# Sensors.net
KiCad netlist of a schematic drawn in Altium Designer
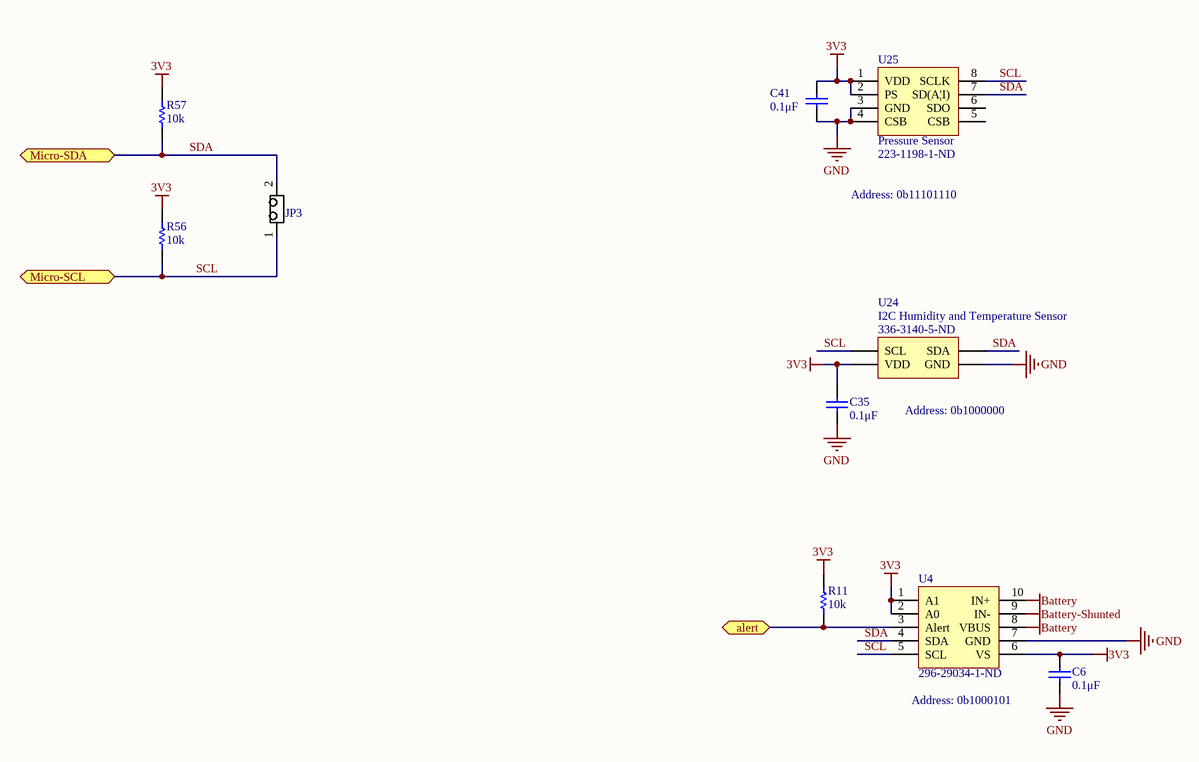
[diagram p0: Sensors.SchDoc]

(export (version "E")
  (design (tool "Eeschema 10.0.6"))
  (components
    (comp (ref "C6")
      (value "0.1μF")
      (footprint "CAPC1608N(0603\")")
      (description "Capacitor, Ceramic, 100V, +/- 10%, 0603 SMD, X7R")
      (fields
        (field (name "MFG") "TDK")
        (field (name "PUBLISHER") "AUVic")
        (field (name "CREATED BY") "Ashwin Sira")
      )
      (libsource (lib "AUVic_Integrated_Library_Capacitors") (part "0.1uF 100V 0603 SMD, Ceramic"))
    )
    (comp (ref "C35")
      (value "0.1μF")
      (footprint "CAPC1608N(0603\")")
      (description "Capacitor, Ceramic, 100V, +/- 10%, 0603 SMD, X7R")
      (fields
        (field (name "MFG") "TDK")
        (field (name "PUBLISHER") "AUVic")
        (field (name "CREATED BY") "Ashwin Sira")
      )
      (libsource (lib "AUVic_Integrated_Library_Capacitors") (part "0.1uF 100V 0603 SMD, Ceramic"))
    )
    (comp (ref "C41")
      (value "0.1μF")
      (footprint "CAPC1608N(0603\")")
      (description "Capacitor, Ceramic, 100V, +/- 10%, 0603 SMD, X7R")
      (fields
        (field (name "MFG") "TDK")
        (field (name "PUBLISHER") "AUVic")
        (field (name "CREATED BY") "Ashwin Sira")
      )
      (libsource (lib "AUVic_Integrated_Library_Capacitors") (part "0.1uF 100V 0603 SMD, Ceramic"))
    )
    (comp (ref "JP3")
      (value "1X2 Pin Head")
      (footprint "2X1 Males Header")
      (fields (field (name "MADE BY") "Andy Bates"))
      (libsource (lib "AUVic_Schematic_Library_Connectors") (part "1x2 Male Header"))
    )
    (comp (ref "R11")
      (value "10k")
      (footprint "RESC1608N(0603\")")
      (description "10kR, 1%, 1/10W, 0603 SMD")
      (fields (field (name "MADE BY") "Ashwin Sira"))
      (libsource (lib "AUVic_Integrated_Library_Resistors") (part "10kR, 1%, 1/10W, 0603 SMD"))
    )
    (comp (ref "R56")
      (value "10k")
      (footprint "RESC1608N(0603\")")
      (description "10kR, 1%, 1/10W, 0603 SMD")
      (fields (field (name "MADE BY") "Ashwin Sira"))
      (libsource (lib "AUVic_Integrated_Library_Resistors") (part "10kR, 1%, 1/10W, 0603 SMD"))
    )
    (comp (ref "R57")
      (value "10k")
      (footprint "RESC1608N(0603\")")
      (description "10kR, 1%, 1/10W, 0603 SMD")
      (fields (field (name "MADE BY") "Ashwin Sira"))
      (libsource (lib "AUVic_Integrated_Library_Resistors") (part "10kR, 1%, 1/10W, 0603 SMD"))
    )
    (comp (ref "U4")
      (value "High side current sensor")
      (footprint "MSOP-10")
      (description "0-36V High side current sensor")
      (fields (field (name "SUPPLIER PART NUMBER 1") "296-29034-1-ND") (field (name "MADE BY") "Andy Bates"))
      (libsource (lib "AUVic_Schematic_Library_Sensors") (part "INA226AIDGSR, Current Sensor, High Side"))
    )
    (comp (ref "U24")
      (value "I2C Humidity and Temperature Sensor")
      (footprint "QFN-6")
      (fields (field (name "SUPPLIER PART NUMBER 1") "336-3140-5-ND") (field (name "MADE BY") "Andy Bates"))
      (libsource (lib "AUVic_Integrated_Library_Sensors") (part "Si700XX"))
    )
    (comp (ref "U25")
      (value "Pressure Sensor")
      (footprint "TE Pressure Sensor (MS560702BA03-50)")
      (description "1kPa to 120 kPa")
      (fields (field (name "SUPPLIER PART NUMBER 1") "223-1198-1-ND") (field (name "MADE BY") "Andy Bates"))
      (libsource (lib "AUVic_Schematic_Library_Sensors") (part "MS560702BA03-50 Pressure Sensor"))
    )
  )
  (nets
    (net (code "1") (name "/SCL") (class "Default")
      (node (ref "JP3") (pin "1") (pinfunction "1_1") (pintype "passive"))
      (node (ref "R56") (pin "1") (pinfunction "1_1") (pintype "passive"))
      (node (ref "U24") (pin "6") (pinfunction "SCL_6") (pintype "passive"))
      (node (ref "U25") (pin "8") (pinfunction "SCLK_8") (pintype "passive"))
      (node (ref "U4") (pin "5") (pinfunction "SCL_5") (pintype "passive"))
    )
    (net (code "2") (name "/SDA") (class "Default")
      (node (ref "JP3") (pin "2") (pinfunction "2_2") (pintype "passive"))
      (node (ref "R57") (pin "1") (pinfunction "1_1") (pintype "passive"))
      (node (ref "U24") (pin "1") (pinfunction "SDA_1") (pintype "passive"))
      (node (ref "U25") (pin "7") (pinfunction "SD(A¦I)_7") (pintype "passive"))
      (node (ref "U4") (pin "4") (pinfunction "SDA_4") (pintype "passive"))
    )
    (net (code "3") (name "/alert") (class "Default")
      (node (ref "R11") (pin "1") (pinfunction "1_1") (pintype "passive"))
      (node (ref "U4") (pin "3") (pinfunction "Alert_3") (pintype "passive"))
    )
    (net (code "4") (name "3V3") (class "Default")
      (node (ref "C35") (pin "1") (pinfunction "Anode_1") (pintype "passive"))
      (node (ref "C41") (pin "2") (pinfunction "Cathode_2") (pintype "passive"))
      (node (ref "C6") (pin "1") (pinfunction "Anode_1") (pintype "passive"))
      (node (ref "R11") (pin "2") (pinfunction "2_2") (pintype "passive"))
      (node (ref "R56") (pin "2") (pinfunction "2_2") (pintype "passive"))
      (node (ref "R57") (pin "2") (pinfunction "2_2") (pintype "passive"))
      (node (ref "U24") (pin "5") (pinfunction "VDD_5") (pintype "passive"))
      (node (ref "U25") (pin "1") (pinfunction "VDD_1") (pintype "passive"))
      (node (ref "U25") (pin "2") (pinfunction "PS_2") (pintype "passive"))
      (node (ref "U4") (pin "1") (pinfunction "A1_1") (pintype "passive"))
      (node (ref "U4") (pin "2") (pinfunction "A0_2") (pintype "passive"))
      (node (ref "U4") (pin "6") (pinfunction "VS_6") (pintype "passive"))
    )
    (net (code "5") (name "Battery") (class "Default")
      (node (ref "U4") (pin "10") (pinfunction "IN+_10") (pintype "passive"))
      (node (ref "U4") (pin "8") (pinfunction "VBUS_8") (pintype "passive"))
    )
    (net (code "6") (name "Battery-Shunted") (class "Default")
      (node (ref "U4") (pin "9") (pinfunction "IN-_9") (pintype "passive"))
    )
    (net (code "7") (name "GND") (class "Default")
      (node (ref "C35") (pin "2") (pinfunction "Cathode_2") (pintype "passive"))
      (node (ref "C41") (pin "1") (pinfunction "Anode_1") (pintype "passive"))
      (node (ref "C6") (pin "2") (pinfunction "Cathode_2") (pintype "passive"))
      (node (ref "U24") (pin "2") (pinfunction "GND_2") (pintype "passive"))
      (node (ref "U25") (pin "3") (pinfunction "GND_3") (pintype "passive"))
      (node (ref "U25") (pin "4") (pinfunction "CSB_4") (pintype "passive"))
      (node (ref "U4") (pin "7") (pinfunction "GND_7") (pintype "passive"))
    )
    (net (code "8") (name "unconnected-(U25-CSB-Pad5)") (class "Default")
      (node (ref "U25") (pin "5") (pinfunction "CSB_5") (pintype "passive"))
    )
    (net (code "9") (name "unconnected-(U25-SDO-Pad6)") (class "Default")
      (node (ref "U25") (pin "6") (pinfunction "SDO_6") (pintype "passive"))
    )
  )
)
